# MotorDrivers.net
KiCad netlist of a schematic drawn in Altium Designer
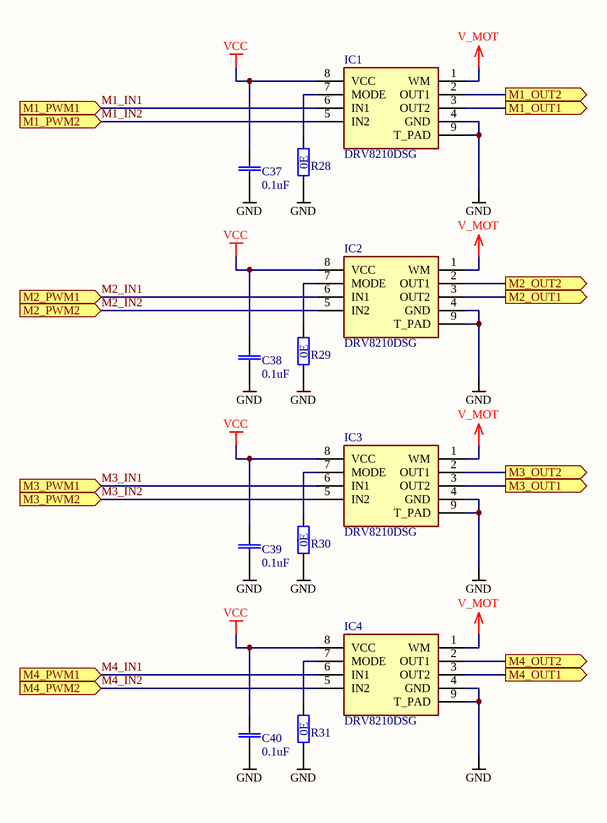
[diagram p0: MotorDrivers.SchDoc]

(export (version "E")
  (design (tool "Eeschema 10.0.6"))
  (components
    (comp (ref "C37")
      (value "0.1uF")
      (footprint "CAP0402")
      (fields (field (name "MANUFACTURER") "Samsung Electro-Mechanics"))
      (libsource (lib "Schematic") (part "CAP_0402"))
    )
    (comp (ref "C38")
      (value "0.1uF")
      (footprint "CAP0402")
      (fields (field (name "MANUFACTURER") "Samsung Electro-Mechanics"))
      (libsource (lib "Schematic") (part "CAP_0402"))
    )
    (comp (ref "C39")
      (value "0.1uF")
      (footprint "CAP0402")
      (fields (field (name "MANUFACTURER") "Samsung Electro-Mechanics"))
      (libsource (lib "Schematic") (part "CAP_0402"))
    )
    (comp (ref "C40")
      (value "0.1uF")
      (footprint "CAP0402")
      (fields (field (name "MANUFACTURER") "Samsung Electro-Mechanics"))
      (libsource (lib "Schematic") (part "CAP_0402"))
    )
    (comp (ref "IC1")
      (value "DRV8210DSG")
      (footprint "WSON8(DRV8210)")
      (fields (field (name "MANUFACTURER") "Texas Instruments"))
      (libsource (lib "Schematic") (part "DRV8210DSG"))
    )
    (comp (ref "IC2")
      (value "DRV8210DSG")
      (footprint "WSON8(DRV8210)")
      (fields (field (name "MANUFACTURER") "Texas Instruments"))
      (libsource (lib "Schematic") (part "DRV8210DSG"))
    )
    (comp (ref "IC3")
      (value "DRV8210DSG")
      (footprint "WSON8(DRV8210)")
      (fields (field (name "MANUFACTURER") "Texas Instruments"))
      (libsource (lib "Schematic") (part "DRV8210DSG"))
    )
    (comp (ref "IC4")
      (value "DRV8210DSG")
      (footprint "WSON8(DRV8210)")
      (fields (field (name "MANUFACTURER") "Texas Instruments"))
      (libsource (lib "Schematic") (part "DRV8210DSG"))
    )
    (comp (ref "R28")
      (value "0E")
      (footprint "RES0402")
      (fields (field (name "MANUFACTURER") "YAGEO"))
      (libsource (lib "Schematic") (part "RES_0402"))
    )
    (comp (ref "R29")
      (value "0E")
      (footprint "RES0402")
      (fields (field (name "MANUFACTURER") "YAGEO"))
      (libsource (lib "Schematic") (part "RES_0402"))
    )
    (comp (ref "R30")
      (value "0E")
      (footprint "RES0402")
      (fields (field (name "MANUFACTURER") "YAGEO"))
      (libsource (lib "Schematic") (part "RES_0402"))
    )
    (comp (ref "R31")
      (value "0E")
      (footprint "RES0402")
      (fields (field (name "MANUFACTURER") "YAGEO"))
      (libsource (lib "Schematic") (part "RES_0402"))
    )
  )
  (nets
    (net (code "1") (name "/M1_IN1") (class "Default")
      (node (ref "IC1") (pin "6") (pinfunction "IN1_6") (pintype "passive"))
    )
    (net (code "2") (name "/M1_IN2") (class "Default")
      (node (ref "IC1") (pin "5") (pinfunction "IN2_5") (pintype "passive"))
    )
    (net (code "3") (name "/M1_OUT1") (class "Default")
      (node (ref "IC1") (pin "3") (pinfunction "OUT2_3") (pintype "passive"))
    )
    (net (code "4") (name "/M1_OUT2") (class "Default")
      (node (ref "IC1") (pin "2") (pinfunction "OUT1_2") (pintype "passive"))
    )
    (net (code "5") (name "/M2_IN1") (class "Default")
      (node (ref "IC2") (pin "6") (pinfunction "IN1_6") (pintype "passive"))
    )
    (net (code "6") (name "/M2_IN2") (class "Default")
      (node (ref "IC2") (pin "5") (pinfunction "IN2_5") (pintype "passive"))
    )
    (net (code "7") (name "/M2_OUT1") (class "Default")
      (node (ref "IC2") (pin "3") (pinfunction "OUT2_3") (pintype "passive"))
    )
    (net (code "8") (name "/M2_OUT2") (class "Default")
      (node (ref "IC2") (pin "2") (pinfunction "OUT1_2") (pintype "passive"))
    )
    (net (code "9") (name "/M3_IN1") (class "Default")
      (node (ref "IC3") (pin "6") (pinfunction "IN1_6") (pintype "passive"))
    )
    (net (code "10") (name "/M3_IN2") (class "Default")
      (node (ref "IC3") (pin "5") (pinfunction "IN2_5") (pintype "passive"))
    )
    (net (code "11") (name "/M3_OUT1") (class "Default")
      (node (ref "IC3") (pin "3") (pinfunction "OUT2_3") (pintype "passive"))
    )
    (net (code "12") (name "/M3_OUT2") (class "Default")
      (node (ref "IC3") (pin "2") (pinfunction "OUT1_2") (pintype "passive"))
    )
    (net (code "13") (name "/M4_IN1") (class "Default")
      (node (ref "IC4") (pin "6") (pinfunction "IN1_6") (pintype "passive"))
    )
    (net (code "14") (name "/M4_IN2") (class "Default")
      (node (ref "IC4") (pin "5") (pinfunction "IN2_5") (pintype "passive"))
    )
    (net (code "15") (name "/M4_OUT1") (class "Default")
      (node (ref "IC4") (pin "3") (pinfunction "OUT2_3") (pintype "passive"))
    )
    (net (code "16") (name "/M4_OUT2") (class "Default")
      (node (ref "IC4") (pin "2") (pinfunction "OUT1_2") (pintype "passive"))
    )
    (net (code "17") (name "GND") (class "Default")
      (node (ref "C37") (pin "1") (pinfunction "1_1") (pintype "passive"))
      (node (ref "C38") (pin "1") (pinfunction "1_1") (pintype "passive"))
      (node (ref "C39") (pin "1") (pinfunction "1_1") (pintype "passive"))
      (node (ref "C40") (pin "1") (pinfunction "1_1") (pintype "passive"))
      (node (ref "IC1") (pin "4") (pinfunction "GND_4") (pintype "passive"))
      (node (ref "IC1") (pin "9") (pinfunction "T_PAD_9") (pintype "passive"))
      (node (ref "IC2") (pin "4") (pinfunction "GND_4") (pintype "passive"))
      (node (ref "IC2") (pin "9") (pinfunction "T_PAD_9") (pintype "passive"))
      (node (ref "IC3") (pin "4") (pinfunction "GND_4") (pintype "passive"))
      (node (ref "IC3") (pin "9") (pinfunction "T_PAD_9") (pintype "passive"))
      (node (ref "IC4") (pin "4") (pinfunction "GND_4") (pintype "passive"))
      (node (ref "IC4") (pin "9") (pinfunction "T_PAD_9") (pintype "passive"))
      (node (ref "R28") (pin "1") (pinfunction "1_1") (pintype "passive"))
      (node (ref "R29") (pin "1") (pinfunction "1_1") (pintype "passive"))
      (node (ref "R30") (pin "1") (pinfunction "1_1") (pintype "passive"))
      (node (ref "R31") (pin "1") (pinfunction "1_1") (pintype "passive"))
    )
    (net (code "18") (name "Net-(IC1-MODE)") (class "Default")
      (node (ref "IC1") (pin "7") (pinfunction "MODE_7") (pintype "passive"))
      (node (ref "R28") (pin "2") (pinfunction "2_2") (pintype "passive"))
    )
    (net (code "19") (name "Net-(IC2-MODE)") (class "Default")
      (node (ref "IC2") (pin "7") (pinfunction "MODE_7") (pintype "passive"))
      (node (ref "R29") (pin "2") (pinfunction "2_2") (pintype "passive"))
    )
    (net (code "20") (name "Net-(IC3-MODE)") (class "Default")
      (node (ref "IC3") (pin "7") (pinfunction "MODE_7") (pintype "passive"))
      (node (ref "R30") (pin "2") (pinfunction "2_2") (pintype "passive"))
    )
    (net (code "21") (name "Net-(IC4-MODE)") (class "Default")
      (node (ref "IC4") (pin "7") (pinfunction "MODE_7") (pintype "passive"))
      (node (ref "R31") (pin "2") (pinfunction "2_2") (pintype "passive"))
    )
    (net (code "22") (name "VCC") (class "Default")
      (node (ref "C37") (pin "2") (pinfunction "2_2") (pintype "passive"))
      (node (ref "C38") (pin "2") (pinfunction "2_2") (pintype "passive"))
      (node (ref "C39") (pin "2") (pinfunction "2_2") (pintype "passive"))
      (node (ref "C40") (pin "2") (pinfunction "2_2") (pintype "passive"))
      (node (ref "IC1") (pin "8") (pinfunction "VCC_8") (pintype "passive"))
      (node (ref "IC2") (pin "8") (pinfunction "VCC_8") (pintype "passive"))
      (node (ref "IC3") (pin "8") (pinfunction "VCC_8") (pintype "passive"))
      (node (ref "IC4") (pin "8") (pinfunction "VCC_8") (pintype "passive"))
    )
    (net (code "23") (name "V_MOT") (class "Default")
      (node (ref "IC1") (pin "1") (pinfunction "WM_1") (pintype "passive"))
      (node (ref "IC2") (pin "1") (pinfunction "WM_1") (pintype "passive"))
      (node (ref "IC3") (pin "1") (pinfunction "WM_1") (pintype "passive"))
      (node (ref "IC4") (pin "1") (pinfunction "WM_1") (pintype "passive"))
    )
  )
)
